# DSP_s.net
KiCad netlist of a schematic drawn in Altium Designer
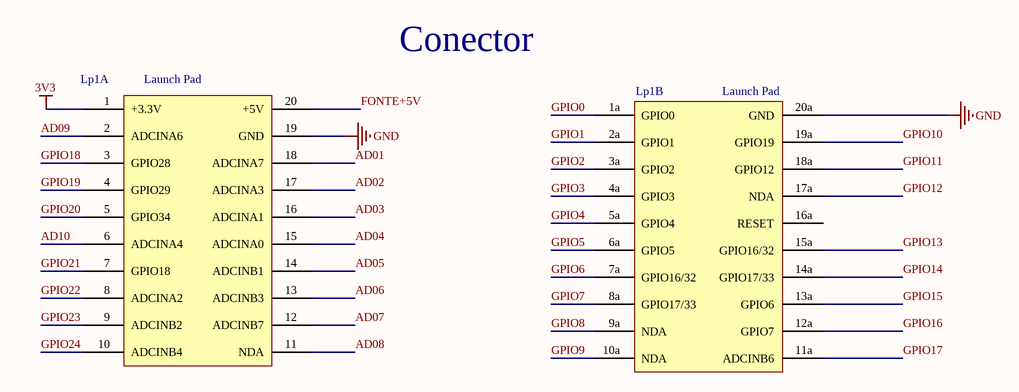
[diagram p0: DSP's.SchDoc]

(export (version "E")
  (design (tool "Eeschema 10.0.6"))
  (components
    (comp (ref "Lp1")
      (value "Launch Pad")
      (footprint "LAUNCHPAD_28xxx")
      (libsource (lib "Miscellaneous_Connectors_Integrated_Library") (part "LaunchPad_28xxx"))
    )
  )
  (nets
    (net (code "1") (name "/AD01") (class "Default")
      (node (ref "Lp1") (pin "18") (pinfunction "ADCINA7_18") (pintype "passive"))
    )
    (net (code "2") (name "/AD02") (class "Default")
      (node (ref "Lp1") (pin "17") (pinfunction "ADCINA3_17") (pintype "passive"))
    )
    (net (code "3") (name "/AD03") (class "Default")
      (node (ref "Lp1") (pin "16") (pinfunction "ADCINA1_16") (pintype "passive"))
    )
    (net (code "4") (name "/AD04") (class "Default")
      (node (ref "Lp1") (pin "15") (pinfunction "ADCINA0_15") (pintype "passive"))
    )
    (net (code "5") (name "/AD05") (class "Default")
      (node (ref "Lp1") (pin "14") (pinfunction "ADCINB1_14") (pintype "passive"))
    )
    (net (code "6") (name "/AD06") (class "Default")
      (node (ref "Lp1") (pin "13") (pinfunction "ADCINB3_13") (pintype "passive"))
    )
    (net (code "7") (name "/AD07") (class "Default")
      (node (ref "Lp1") (pin "12") (pinfunction "ADCINB7_12") (pintype "passive"))
    )
    (net (code "8") (name "/AD08") (class "Default")
      (node (ref "Lp1") (pin "11") (pinfunction "NDA_11") (pintype "passive"))
    )
    (net (code "9") (name "/AD09") (class "Default")
      (node (ref "Lp1") (pin "2") (pinfunction "ADCINA6_2") (pintype "passive"))
    )
    (net (code "10") (name "/AD10") (class "Default")
      (node (ref "Lp1") (pin "6") (pinfunction "ADCINA4_6") (pintype "passive"))
    )
    (net (code "11") (name "/FONTE+5V") (class "Default")
      (node (ref "Lp1") (pin "20") (pinfunction "+5V_20") (pintype "passive"))
    )
    (net (code "12") (name "/GPIO0") (class "Default")
      (node (ref "Lp1") (pin "1a") (pinfunction "GPIO0_1a") (pintype "passive"))
    )
    (net (code "13") (name "/GPIO1") (class "Default")
      (node (ref "Lp1") (pin "2a") (pinfunction "GPIO1_2a") (pintype "passive"))
    )
    (net (code "14") (name "/GPIO2") (class "Default")
      (node (ref "Lp1") (pin "3a") (pinfunction "GPIO2_3a") (pintype "passive"))
    )
    (net (code "15") (name "/GPIO3") (class "Default")
      (node (ref "Lp1") (pin "4a") (pinfunction "GPIO3_4a") (pintype "passive"))
    )
    (net (code "16") (name "/GPIO4") (class "Default")
      (node (ref "Lp1") (pin "5a") (pinfunction "GPIO4_5a") (pintype "passive"))
    )
    (net (code "17") (name "/GPIO5") (class "Default")
      (node (ref "Lp1") (pin "6a") (pinfunction "GPIO5_6a") (pintype "passive"))
    )
    (net (code "18") (name "/GPIO6") (class "Default")
      (node (ref "Lp1") (pin "7a") (pinfunction "GPIO16/32_7a") (pintype "passive"))
    )
    (net (code "19") (name "/GPIO7") (class "Default")
      (node (ref "Lp1") (pin "8a") (pinfunction "GPIO17/33_8a") (pintype "passive"))
    )
    (net (code "20") (name "/GPIO8") (class "Default")
      (node (ref "Lp1") (pin "9a") (pinfunction "NDA_9a") (pintype "passive"))
    )
    (net (code "21") (name "/GPIO9") (class "Default")
      (node (ref "Lp1") (pin "10a") (pinfunction "NDA_10a") (pintype "passive"))
    )
    (net (code "22") (name "/GPIO10") (class "Default")
      (node (ref "Lp1") (pin "19a") (pinfunction "GPIO19_19a") (pintype "passive"))
    )
    (net (code "23") (name "/GPIO11") (class "Default")
      (node (ref "Lp1") (pin "18a") (pinfunction "GPIO12_18a") (pintype "passive"))
    )
    (net (code "24") (name "/GPIO12") (class "Default")
      (node (ref "Lp1") (pin "17a") (pinfunction "NDA_17a") (pintype "passive"))
    )
    (net (code "25") (name "/GPIO13") (class "Default")
      (node (ref "Lp1") (pin "15a") (pinfunction "GPIO16/32_15a") (pintype "passive"))
    )
    (net (code "26") (name "/GPIO14") (class "Default")
      (node (ref "Lp1") (pin "14a") (pinfunction "GPIO17/33_14a") (pintype "passive"))
    )
    (net (code "27") (name "/GPIO15") (class "Default")
      (node (ref "Lp1") (pin "13a") (pinfunction "GPIO6_13a") (pintype "passive"))
    )
    (net (code "28") (name "/GPIO16") (class "Default")
      (node (ref "Lp1") (pin "12a") (pinfunction "GPIO7_12a") (pintype "passive"))
    )
    (net (code "29") (name "/GPIO17") (class "Default")
      (node (ref "Lp1") (pin "11a") (pinfunction "ADCINB6_11a") (pintype "passive"))
    )
    (net (code "30") (name "/GPIO18") (class "Default")
      (node (ref "Lp1") (pin "3") (pinfunction "GPIO28_3") (pintype "passive"))
    )
    (net (code "31") (name "/GPIO19") (class "Default")
      (node (ref "Lp1") (pin "4") (pinfunction "GPIO29_4") (pintype "passive"))
    )
    (net (code "32") (name "/GPIO20") (class "Default")
      (node (ref "Lp1") (pin "5") (pinfunction "GPIO34_5") (pintype "passive"))
    )
    (net (code "33") (name "/GPIO21") (class "Default")
      (node (ref "Lp1") (pin "7") (pinfunction "GPIO18_7") (pintype "passive"))
    )
    (net (code "34") (name "/GPIO22") (class "Default")
      (node (ref "Lp1") (pin "8") (pinfunction "ADCINA2_8") (pintype "passive"))
    )
    (net (code "35") (name "/GPIO23") (class "Default")
      (node (ref "Lp1") (pin "9") (pinfunction "ADCINB2_9") (pintype "passive"))
    )
    (net (code "36") (name "/GPIO24") (class "Default")
      (node (ref "Lp1") (pin "10") (pinfunction "ADCINB4_10") (pintype "passive"))
    )
    (net (code "37") (name "3V3") (class "Default")
      (node (ref "Lp1") (pin "1") (pinfunction "+3.3V_1") (pintype "passive"))
    )
    (net (code "38") (name "GND") (class "Default")
      (node (ref "Lp1") (pin "19") (pinfunction "GND_19") (pintype "passive"))
      (node (ref "Lp1") (pin "20a") (pinfunction "GND_20a") (pintype "passive"))
    )
    (net (code "39") (name "unconnected-(Lp1B-RESET-Pad16a)") (class "Default")
      (node (ref "Lp1") (pin "16a") (pinfunction "RESET_16a") (pintype "passive"))
    )
  )
)
